# Power.net
KiCad netlist of a schematic drawn in Altium Designer
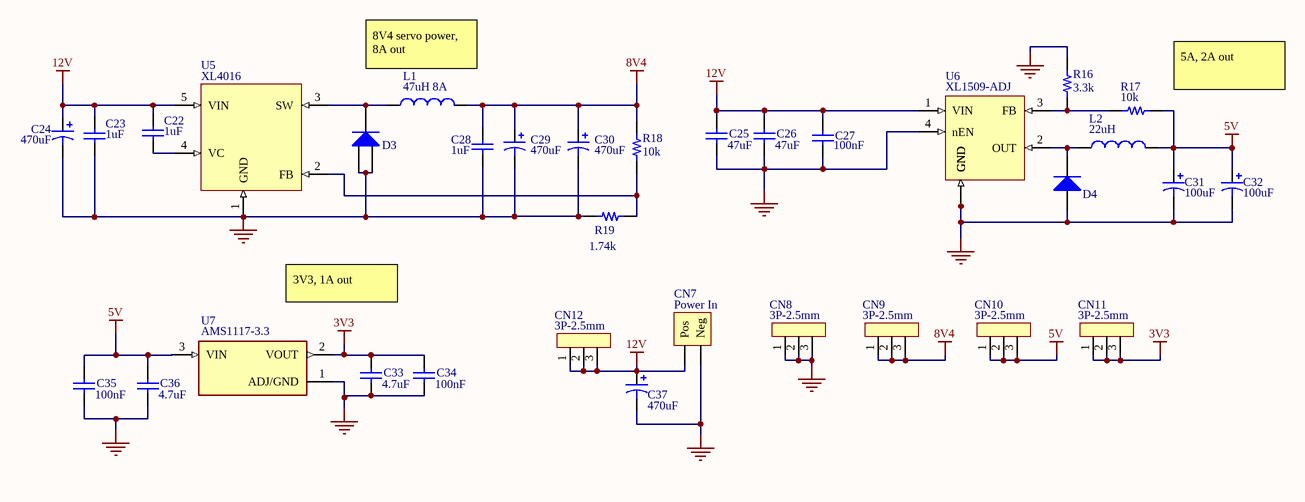
[diagram p0: Power.SchDoc]

(export (version "E")
  (design (tool "Eeschema 10.0.6"))
  (components
    (comp (ref "C22")
      (value "1uF")
      (footprint "0402")
      (fields (field (name "Comment") "Cap") (field (name "PUBLISHER") "Altium Limited"))
      (libsource (lib "Parts") (part "Cap"))
    )
    (comp (ref "C23")
      (value "1uF")
      (footprint "0402")
      (fields (field (name "Comment") "Cap") (field (name "PUBLISHER") "Altium Limited"))
      (libsource (lib "Parts") (part "Cap"))
    )
    (comp (ref "C24")
      (value "470uF")
      (footprint "10x12mm-Electrolytic")
      (libsource (lib "Parts") (part "Polarised Capacitor"))
    )
    (comp (ref "C25")
      (value "47uF")
      (footprint "1206")
      (fields (field (name "Comment") "Cap") (field (name "PUBLISHER") "Altium Limited"))
      (libsource (lib "Parts") (part "Cap"))
    )
    (comp (ref "C26")
      (value "47uF")
      (footprint "1206")
      (fields (field (name "Comment") "Cap") (field (name "PUBLISHER") "Altium Limited"))
      (libsource (lib "Parts") (part "Cap"))
    )
    (comp (ref "C27")
      (value "100nF")
      (footprint "0402")
      (fields (field (name "Comment") "Cap") (field (name "PUBLISHER") "Altium Limited"))
      (libsource (lib "Parts") (part "Cap"))
    )
    (comp (ref "C28")
      (value "1uF")
      (footprint "0402")
      (fields (field (name "Comment") "Cap") (field (name "PUBLISHER") "Altium Limited"))
      (libsource (lib "Parts") (part "Cap"))
    )
    (comp (ref "C29")
      (value "470uF")
      (footprint "10x12mm-Electrolytic")
      (libsource (lib "Parts") (part "Polarised Capacitor"))
    )
    (comp (ref "C30")
      (value "470uF")
      (footprint "10x12mm-Electrolytic")
      (libsource (lib "Parts") (part "Polarised Capacitor"))
    )
    (comp (ref "C31")
      (value "100uF")
      (footprint "8x10.2 Cap")
      (libsource (lib "Parts") (part "Polarised Capacitor"))
    )
    (comp (ref "C32")
      (value "100uF")
      (footprint "8x10.2 Cap")
      (libsource (lib "Parts") (part "Polarised Capacitor"))
    )
    (comp (ref "C33")
      (value "4.7uF")
      (footprint "0805 - duplicate")
      (fields (field (name "Comment") "Cap") (field (name "PUBLISHER") "Altium Limited"))
      (libsource (lib "Parts") (part "Cap"))
    )
    (comp (ref "C34")
      (value "100nF")
      (footprint "0402")
      (fields (field (name "Comment") "Cap") (field (name "PUBLISHER") "Altium Limited"))
      (libsource (lib "Parts") (part "Cap"))
    )
    (comp (ref "C35")
      (value "100nF")
      (footprint "0402")
      (fields (field (name "Comment") "Cap") (field (name "PUBLISHER") "Altium Limited"))
      (libsource (lib "Parts") (part "Cap"))
    )
    (comp (ref "C36")
      (value "4.7uF")
      (footprint "0805 - duplicate")
      (fields (field (name "Comment") "Cap") (field (name "PUBLISHER") "Altium Limited"))
      (libsource (lib "Parts") (part "Cap"))
    )
    (comp (ref "C37")
      (value "470uF")
      (footprint "10x12mm-Electrolytic")
      (libsource (lib "Parts") (part "Polarised Capacitor"))
    )
    (comp (ref "CN7")
      (value "Power In")
      (footprint "Power_Leads")
      (libsource (lib "Parts") (part "JST_Leads_In"))
    )
    (comp (ref "CN8") (value "3P-2.5mm") (footprint "2.5mm-3P") (libsource (lib "Parts") (part "3P-2.5mm")))
    (comp (ref "CN9") (value "3P-2.5mm") (footprint "2.5mm-3P") (libsource (lib "Parts") (part "3P-2.5mm")))
    (comp (ref "CN10") (value "3P-2.5mm") (footprint "2.5mm-3P") (libsource (lib "Parts") (part "3P-2.5mm")))
    (comp (ref "CN11") (value "3P-2.5mm") (footprint "2.5mm-3P") (libsource (lib "Parts") (part "3P-2.5mm")))
    (comp (ref "CN12") (value "3P-2.5mm") (footprint "2.5mm-3P") (libsource (lib "Parts") (part "3P-2.5mm")))
    (comp (ref "D3")
      (value "Diode")
      (footprint "PowerDi5")
      (fields (field (name "PUBLISHER") "Altium Limited"))
      (libsource (lib "Parts") (part "Diode"))
    )
    (comp (ref "D4")
      (value "SS24")
      (footprint "DO-214AA")
      (description "2A Schottky Diode")
      (libsource (lib "Parts") (part "SS24"))
    )
    (comp (ref "L1")
      (value "47uH 8A")
      (footprint "18x16-9-Inductor")
      (description "TMPC1707")
      (libsource (lib "Parts") (part "SMD Inductor 18x16.9"))
    )
    (comp (ref "L2")
      (value "22uH")
      (footprint "71x66-Inductor")
      (libsource (lib "Parts") (part "22uH Inductor, 7.1*6.6"))
    )
    (comp (ref "R16")
      (value "3.3k")
      (footprint "0805 - duplicate")
      (libsource (lib "Parts") (part "Resistor"))
    )
    (comp (ref "R17")
      (value "10k")
      (footprint "0805 - duplicate")
      (libsource (lib "Parts") (part "Resistor"))
    )
    (comp (ref "R18")
      (value "10k")
      (footprint "0805 - duplicate")
      (libsource (lib "Parts") (part "Resistor"))
    )
    (comp (ref "R19")
      (value "1.74k")
      (footprint "0805 - duplicate")
      (libsource (lib "Parts") (part "Resistor"))
    )
    (comp (ref "U5")
      (value "XL4016")
      (footprint "TO220-5L")
      (description "8A Buck COnverter")
      (libsource (lib "Parts") (part "XL4016"))
    )
    (comp (ref "U6")
      (value "XL1509-ADJ")
      (footprint "SOP8-MT3420")
      (libsource (lib "Parts") (part "XL1509-5"))
    )
    (comp (ref "U7")
      (value "AMS1117-3.3")
      (footprint "SOT229P700X180-4N")
      (description "Sot223/Pkg 1-Amp 3.3-Volt Low Drop Out Voltage Regulatator")
      (fields (field (name "MF") "Advanced Monolithic Systems"))
      (libsource (lib "Parts") (part "AMS1117-3.3"))
    )
  )
  (nets
    (net (code "1") (name "3V3") (class "Default")
      (node (ref "C33") (pin "2") (pinfunction "2_2") (pintype "passive"))
      (node (ref "C34") (pin "2") (pinfunction "2_2") (pintype "passive"))
      (node (ref "CN11") (pin "1") (pintype "passive"))
      (node (ref "CN11") (pin "2") (pintype "passive"))
      (node (ref "CN11") (pin "3") (pintype "passive"))
      (node (ref "U7") (pin "2") (pinfunction "VOUT_2") (pintype "output"))
    )
    (net (code "2") (name "5V") (class "Default")
      (node (ref "C31") (pin "1") (pinfunction "1_1") (pintype "passive"))
      (node (ref "C32") (pin "1") (pinfunction "1_1") (pintype "passive"))
      (node (ref "C35") (pin "2") (pinfunction "2_2") (pintype "passive"))
      (node (ref "C36") (pin "2") (pinfunction "2_2") (pintype "passive"))
      (node (ref "CN10") (pin "1") (pintype "passive"))
      (node (ref "CN10") (pin "2") (pintype "passive"))
      (node (ref "CN10") (pin "3") (pintype "passive"))
      (node (ref "L2") (pin "2") (pinfunction "2_2") (pintype "passive"))
      (node (ref "R17") (pin "2") (pinfunction "2_2") (pintype "passive"))
      (node (ref "U7") (pin "3") (pinfunction "VIN_3") (pintype "input"))
    )
    (net (code "3") (name "8V4") (class "Default")
      (node (ref "C28") (pin "2") (pinfunction "2_2") (pintype "passive"))
      (node (ref "C29") (pin "1") (pinfunction "1_1") (pintype "passive"))
      (node (ref "C30") (pin "1") (pinfunction "1_1") (pintype "passive"))
      (node (ref "CN9") (pin "1") (pintype "passive"))
      (node (ref "CN9") (pin "2") (pintype "passive"))
      (node (ref "CN9") (pin "3") (pintype "passive"))
      (node (ref "L1") (pin "2") (pinfunction "2_2") (pintype "passive"))
      (node (ref "R18") (pin "2") (pinfunction "2_2") (pintype "passive"))
    )
    (net (code "4") (name "12V") (class "Default")
      (node (ref "C22") (pin "2") (pinfunction "2_2") (pintype "passive"))
      (node (ref "C23") (pin "2") (pinfunction "2_2") (pintype "passive"))
      (node (ref "C24") (pin "1") (pinfunction "1_1") (pintype "passive"))
      (node (ref "C25") (pin "2") (pinfunction "2_2") (pintype "passive"))
      (node (ref "C26") (pin "2") (pinfunction "2_2") (pintype "passive"))
      (node (ref "C27") (pin "2") (pinfunction "2_2") (pintype "passive"))
      (node (ref "C37") (pin "1") (pinfunction "1_1") (pintype "passive"))
      (node (ref "CN12") (pin "1") (pintype "passive"))
      (node (ref "CN12") (pin "2") (pintype "passive"))
      (node (ref "CN12") (pin "3") (pintype "passive"))
      (node (ref "CN7") (pin "A") (pinfunction "Pos_A") (pintype "passive"))
      (node (ref "U5") (pin "5") (pinfunction "VIN_5") (pintype "input"))
      (node (ref "U6") (pin "1") (pinfunction "VIN_1") (pintype "input"))
    )
    (net (code "5") (name "GND") (class "Default")
      (node (ref "C23") (pin "1") (pinfunction "1_1") (pintype "passive"))
      (node (ref "C24") (pin "2") (pinfunction "2_2") (pintype "passive"))
      (node (ref "C25") (pin "1") (pinfunction "1_1") (pintype "passive"))
      (node (ref "C26") (pin "1") (pinfunction "1_1") (pintype "passive"))
      (node (ref "C27") (pin "1") (pinfunction "1_1") (pintype "passive"))
      (node (ref "C28") (pin "1") (pinfunction "1_1") (pintype "passive"))
      (node (ref "C29") (pin "2") (pinfunction "2_2") (pintype "passive"))
      (node (ref "C30") (pin "2") (pinfunction "2_2") (pintype "passive"))
      (node (ref "C31") (pin "2") (pinfunction "2_2") (pintype "passive"))
      (node (ref "C32") (pin "2") (pinfunction "2_2") (pintype "passive"))
      (node (ref "C33") (pin "1") (pinfunction "1_1") (pintype "passive"))
      (node (ref "C34") (pin "1") (pinfunction "1_1") (pintype "passive"))
      (node (ref "C35") (pin "1") (pinfunction "1_1") (pintype "passive"))
      (node (ref "C36") (pin "1") (pinfunction "1_1") (pintype "passive"))
      (node (ref "C37") (pin "2") (pinfunction "2_2") (pintype "passive"))
      (node (ref "CN7") (pin "K") (pinfunction "Neg_K") (pintype "passive"))
      (node (ref "CN8") (pin "1") (pintype "passive"))
      (node (ref "CN8") (pin "2") (pintype "passive"))
      (node (ref "CN8") (pin "3") (pintype "passive"))
      (node (ref "D3") (pin "1") (pinfunction "A_1") (pintype "passive"))
      (node (ref "D3") (pin "2") (pinfunction "A_2") (pintype "passive"))
      (node (ref "D4") (pin "A") (pinfunction "A_A") (pintype "passive"))
      (node (ref "R16") (pin "2") (pinfunction "2_2") (pintype "passive"))
      (node (ref "R19") (pin "1") (pinfunction "1_1") (pintype "passive"))
      (node (ref "U5") (pin "1") (pinfunction "GND_1") (pintype "input"))
      (node (ref "U6") (pin "4") (pinfunction "nEN_4") (pintype "input"))
      (node (ref "U6") (pin "5") (pinfunction "GND_5") (pintype "input"))
      (node (ref "U6") (pin "6") (pinfunction "GND_6") (pintype "input"))
      (node (ref "U6") (pin "7") (pinfunction "GND_7") (pintype "input"))
      (node (ref "U6") (pin "8") (pinfunction "GND_8") (pintype "input"))
      (node (ref "U7") (pin "1") (pinfunction "ADJ/GND_1") (pintype "power_in"))
    )
    (net (code "6") (name "Net-(D3-K)") (class "Default")
      (node (ref "D3") (pin "3") (pinfunction "K_3") (pintype "passive"))
      (node (ref "L1") (pin "1") (pinfunction "1_1") (pintype "passive"))
      (node (ref "U5") (pin "3") (pinfunction "SW_3") (pintype "input"))
    )
    (net (code "7") (name "Net-(U5-FB)") (class "Default")
      (node (ref "R18") (pin "1") (pinfunction "1_1") (pintype "passive"))
      (node (ref "R19") (pin "2") (pinfunction "2_2") (pintype "passive"))
      (node (ref "U5") (pin "2") (pinfunction "FB_2") (pintype "input"))
    )
    (net (code "8") (name "Net-(U5-VC)") (class "Default")
      (node (ref "C22") (pin "1") (pinfunction "1_1") (pintype "passive"))
      (node (ref "U5") (pin "4") (pinfunction "VC_4") (pintype "input"))
    )
    (net (code "9") (name "Net-(U6-FB)") (class "Default")
      (node (ref "R16") (pin "1") (pinfunction "1_1") (pintype "passive"))
      (node (ref "R17") (pin "1") (pinfunction "1_1") (pintype "passive"))
      (node (ref "U6") (pin "3") (pinfunction "FB_3") (pintype "input"))
    )
    (net (code "10") (name "Net-(U6-OUT)") (class "Default")
      (node (ref "D4") (pin "K") (pinfunction "K_K") (pintype "passive"))
      (node (ref "L2") (pin "1") (pinfunction "1_1") (pintype "passive"))
      (node (ref "U6") (pin "2") (pinfunction "OUT_2") (pintype "input"))
    )
  )
)
